# DC_DC_CONTROL.net
KiCad netlist of a schematic drawn in Altium Designer
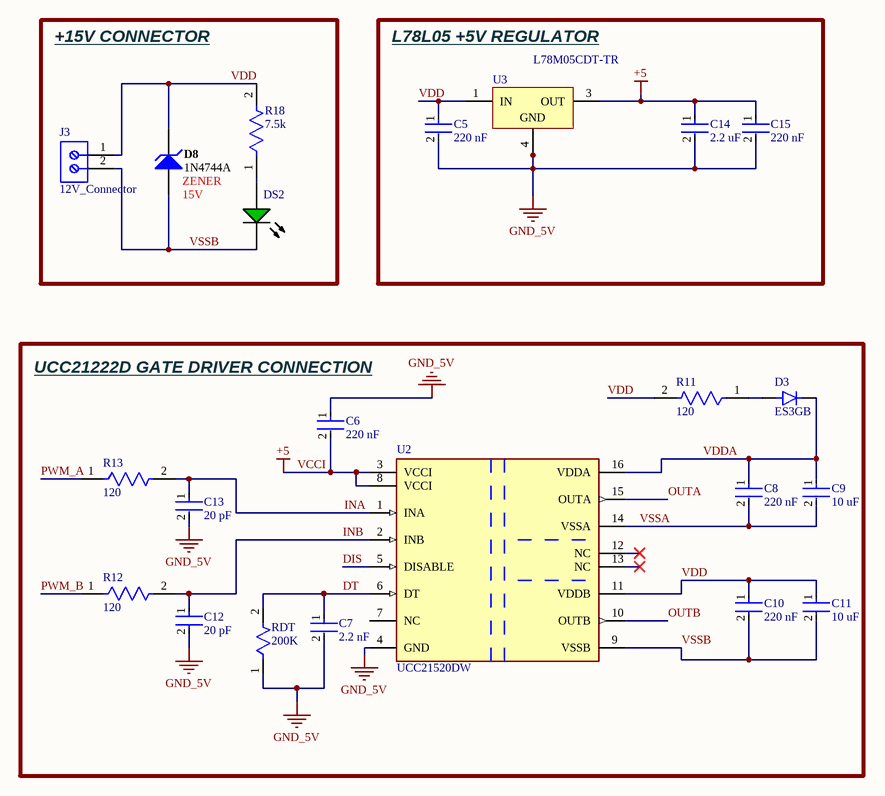
[diagram p0: DC_DC_CONTROL.SchDoc]

(export (version "E")
  (design (tool "Eeschema 10.0.6"))
  (components
    (comp (ref "C5")
      (value "220 nF")
      (footprint "FP-C0805C-DN-MFG")
      (description "CAP CER 0.22UF 50V X7R 0805")
      (fields
        (field (name "MANUFACTURER") "KEMET")
        (field (name "OCTOPART") "https://octopart.com/c0805c224k5ractu-kemet-144670")
      )
      (libsource (lib "Altium Content Vault") (part "b4654b650e69147ec39a6b967a45e02"))
    )
    (comp (ref "C6")
      (value "220 nF")
      (footprint "FP-C0805C-DN-MFG")
      (description "CAP CER 0.22UF 50V X7R 0805")
      (fields
        (field (name "MANUFACTURER") "KEMET")
        (field (name "OCTOPART") "https://octopart.com/c0805c224k5ractu-kemet-144670")
      )
      (libsource (lib "Altium Content Vault") (part "b4654b650e69147ec39a6b967a45e02"))
    )
    (comp (ref "C7")
      (value "2.2 nF")
      (footprint "FP-C0805C-DN-MFG")
      (description "CAP CER 0.22UF 50V X7R 0805")
      (fields
        (field (name "MANUFACTURER") "KEMET")
        (field (name "OCTOPART") "https://octopart.com/c0805c224k5ractu-kemet-144670")
      )
      (libsource (lib "Altium Content Vault") (part "b4654b650e69147ec39a6b967a45e02"))
    )
    (comp (ref "C8")
      (value "220 nF")
      (footprint "FP-C0805C-DN-MFG")
      (description "CAP CER 0.22UF 50V X7R 0805")
      (fields
        (field (name "MANUFACTURER") "KEMET")
        (field (name "OCTOPART") "https://octopart.com/c0805c224k5ractu-kemet-144670")
      )
      (libsource (lib "Altium Content Vault") (part "b4654b650e69147ec39a6b967a45e02"))
    )
    (comp (ref "C9")
      (value "10 uF")
      (footprint "FP-C0805C-DN-MFG")
      (description "CAP CER 0.22UF 50V X7R 0805")
      (fields
        (field (name "MANUFACTURER") "KEMET")
        (field (name "OCTOPART") "https://octopart.com/c0805c224k5ractu-kemet-144670")
      )
      (libsource (lib "Altium Content Vault") (part "b4654b650e69147ec39a6b967a45e02"))
    )
    (comp (ref "C10")
      (value "220 nF")
      (footprint "FP-C0805C-DN-MFG")
      (description "CAP CER 0.22UF 50V X7R 0805")
      (fields
        (field (name "MANUFACTURER") "KEMET")
        (field (name "OCTOPART") "https://octopart.com/c0805c224k5ractu-kemet-144670")
      )
      (libsource (lib "Altium Content Vault") (part "b4654b650e69147ec39a6b967a45e02"))
    )
    (comp (ref "C11")
      (value "10 uF")
      (footprint "FP-C0805C-DN-MFG")
      (description "CAP CER 0.22UF 50V X7R 0805")
      (fields
        (field (name "MANUFACTURER") "KEMET")
        (field (name "OCTOPART") "https://octopart.com/c0805c224k5ractu-kemet-144670")
      )
      (libsource (lib "Altium Content Vault") (part "b4654b650e69147ec39a6b967a45e02"))
    )
    (comp (ref "C12")
      (value "20 pF")
      (footprint "FP-C0805C-DN-MFG")
      (description "CAP CER 0.22UF 50V X7R 0805")
      (fields
        (field (name "MANUFACTURER") "KEMET")
        (field (name "OCTOPART") "https://octopart.com/c0805c224k5ractu-kemet-144670")
      )
      (libsource (lib "Altium Content Vault") (part "b4654b650e69147ec39a6b967a45e02"))
    )
    (comp (ref "C13")
      (value "20 pF")
      (footprint "FP-C0805C-DN-MFG")
      (description "CAP CER 0.22UF 50V X7R 0805")
      (fields
        (field (name "MANUFACTURER") "KEMET")
        (field (name "OCTOPART") "https://octopart.com/c0805c224k5ractu-kemet-144670")
      )
      (libsource (lib "Altium Content Vault") (part "b4654b650e69147ec39a6b967a45e02"))
    )
    (comp (ref "C14")
      (value "2.2 uF")
      (footprint "FP-C0805C-DN-MFG")
      (description "CAP CER 0.22UF 50V X7R 0805")
      (fields
        (field (name "MANUFACTURER") "KEMET")
        (field (name "OCTOPART") "https://octopart.com/c0805c224k5ractu-kemet-144670")
      )
      (libsource (lib "Altium Content Vault") (part "b4654b650e69147ec39a6b967a45e02"))
    )
    (comp (ref "C15")
      (value "220 nF")
      (footprint "FP-C0805C-DN-MFG")
      (description "CAP CER 0.22UF 50V X7R 0805")
      (fields
        (field (name "MANUFACTURER") "KEMET")
        (field (name "OCTOPART") "https://octopart.com/c0805c224k5ractu-kemet-144670")
      )
      (libsource (lib "Altium Content Vault") (part "b4654b650e69147ec39a6b967a45e02"))
    )
    (comp (ref "D3")
      (value "ES3GB")
      (footprint "ES3GB:DIOM4336X265N")
      (fields (field (name "MF") "{'manufacturer': u'Taiwan Semiconductor'}"))
      (libsource (lib "*") (part "ES3GB"))
    )
    (comp (ref "D8")
      (value "1N4744A")
      (footprint "FAIR-DO-41-2_V")
      (description "Zener Diode, 15V, 1W, 5%, -65 to 200 degC, 2-Pin DO-41, Body 2.72 x 5.2 mm, RoHS")
      (fields (field (name "MANUFACTURER") "Fairchild Semiconductor") (field (name "TOLERANCE") "5%"))
      (libsource (lib "Altium Content Vault") (part "FAIR-DZEN-A1K2-2"))
    )
    (comp (ref "DS2")
      (value "HSMG-C170")
      (footprint "AVAG-HSMX-C170_V")
      (description "Chip LED, Green, 2.2 V, -40 to 85 degC, 2-Pin SMD, Pb-Free, Tape and Reel")
      (fields (field (name "MANUFACTURER") "Avago"))
      (libsource (lib "Altium Content Vault") (part "LED_GREEN_A1K2-2"))
    )
    (comp (ref "J3")
      (value "12V_Connector")
      (footprint "691214110002")
      (fields (field (name "VOLTAGE") "300V"))
      (libsource (lib "WurthElectronics2PinTerminalBlock") (part "CMP-1502-02464-2"))
    )
    (comp (ref "R11")
      (value "120")
      (footprint "FP-RC0805-0_6-IPC_C")
      (description "120  1/8W   0805")
      (fields (field (name "TOLERANCE") "1%"))
      (libsource (lib "Altium Content Vault") (part "1029c3af85768c4190bb7ad29bc67b5"))
    )
    (comp (ref "R12")
      (value "120")
      (footprint "FP-RC0805-0_6-IPC_C")
      (description "120  1/8W   0805")
      (fields (field (name "TOLERANCE") "1%"))
      (libsource (lib "Altium Content Vault") (part "1029c3af85768c4190bb7ad29bc67b5"))
    )
    (comp (ref "R13")
      (value "120")
      (footprint "FP-RC0805-0_6-IPC_C")
      (description "120  1/8W   0805")
      (fields (field (name "TOLERANCE") "1%"))
      (libsource (lib "Altium Content Vault") (part "1029c3af85768c4190bb7ad29bc67b5"))
    )
    (comp (ref "R18")
      (value "7.5k")
      (footprint "FP-RC0805-0_6-IPC_C")
      (description "7.5K  1/8W   0805")
      (fields (field (name "TOLERANCE") "1%"))
      (libsource (lib "Altium Content Vault") (part "1029c3af85768c4190bb7ad29bc67b5"))
    )
    (comp (ref "RDT")
      (value "200K")
      (footprint "PCBComponent_1")
      (libsource (lib "RES_0.125W_AXIAL") (part "RES"))
    )
    (comp (ref "U2")
      (value "UCC21520DW")
      (footprint "FP-DW0016B-MFG")
      (description "DGTL ISO 5.7KV GATE DRVR 16SOIC")
      (libsource (lib "Altium Content Vault") (part "6a37a0897a27c2327358918c0ee180b"))
    )
    (comp (ref "U3")
      (value "L78M05CDT-TR")
      (footprint "TO-252_L")
      (description "Positive Voltage Regulator, 5V, 3-Pin DPAK, Tape and Reel")
      (libsource (lib "Altium Content Vault") (part "PM-REG-L4940-SOT3"))
    )
  )
  (nets
    (net (code "1") (name "+5") (class "Default")
      (node (ref "C14") (pin "1") (pinfunction "1_1") (pintype "passive"))
      (node (ref "C15") (pin "1") (pinfunction "1_1") (pintype "passive"))
      (node (ref "C6") (pin "2") (pinfunction "2_2") (pintype "passive"))
      (node (ref "U2") (pin "3") (pinfunction "VCCI_3") (pintype "power_in"))
      (node (ref "U2") (pin "8") (pinfunction "VCCI_8") (pintype "power_in"))
      (node (ref "U3") (pin "3") (pinfunction "OUT_3") (pintype "power_in"))
    )
    (net (code "2") (name "/DIS") (class "Default")
      (node (ref "U2") (pin "5") (pinfunction "DISABLE_5") (pintype "input"))
    )
    (net (code "3") (name "/DT") (class "Default")
      (node (ref "C7") (pin "1") (pinfunction "1_1") (pintype "passive"))
      (node (ref "RDT") (pin "2") (pinfunction "2_2") (pintype "passive"))
      (node (ref "U2") (pin "6") (pinfunction "DT_6") (pintype "input"))
    )
    (net (code "4") (name "/INA") (class "Default")
      (node (ref "C13") (pin "1") (pinfunction "1_1") (pintype "passive"))
      (node (ref "R13") (pin "2") (pinfunction "2_2") (pintype "passive"))
      (node (ref "U2") (pin "1") (pinfunction "INA_1") (pintype "input"))
    )
    (net (code "5") (name "/INB") (class "Default")
      (node (ref "C12") (pin "1") (pinfunction "1_1") (pintype "passive"))
      (node (ref "R12") (pin "2") (pinfunction "2_2") (pintype "passive"))
      (node (ref "U2") (pin "2") (pinfunction "INB_2") (pintype "input"))
    )
    (net (code "6") (name "/OUTA") (class "Default")
      (node (ref "U2") (pin "15") (pinfunction "OUTA_15") (pintype "output"))
    )
    (net (code "7") (name "/OUTB") (class "Default")
      (node (ref "U2") (pin "10") (pinfunction "OUTB_10") (pintype "output"))
    )
    (net (code "8") (name "/PWM_A") (class "Default")
      (node (ref "R13") (pin "1") (pinfunction "1_1") (pintype "passive"))
    )
    (net (code "9") (name "/PWM_B") (class "Default")
      (node (ref "R12") (pin "1") (pinfunction "1_1") (pintype "passive"))
    )
    (net (code "10") (name "/VDD") (class "Default")
      (node (ref "C10") (pin "1") (pinfunction "1_1") (pintype "passive"))
      (node (ref "C11") (pin "1") (pinfunction "1_1") (pintype "passive"))
      (node (ref "C5") (pin "1") (pinfunction "1_1") (pintype "passive"))
      (node (ref "D8") (pin "2") (pinfunction "K_2") (pintype "passive"))
      (node (ref "J3") (pin "1") (pinfunction "1_1") (pintype "passive"))
      (node (ref "R11") (pin "2") (pinfunction "2_2") (pintype "passive"))
      (node (ref "R18") (pin "2") (pinfunction "2_2") (pintype "passive"))
      (node (ref "U2") (pin "11") (pinfunction "VDDB_11") (pintype "power_in"))
      (node (ref "U3") (pin "1") (pinfunction "IN_1") (pintype "power_in"))
    )
    (net (code "11") (name "/VDDA") (class "Default")
      (node (ref "C8") (pin "1") (pinfunction "1_1") (pintype "passive"))
      (node (ref "C9") (pin "1") (pinfunction "1_1") (pintype "passive"))
      (node (ref "D3") (pin "C") (pinfunction "K_C") (pintype "passive"))
      (node (ref "U2") (pin "16") (pinfunction "VDDA_16") (pintype "power_in"))
    )
    (net (code "12") (name "/VSSA") (class "Default")
      (node (ref "C8") (pin "2") (pinfunction "2_2") (pintype "passive"))
      (node (ref "C9") (pin "2") (pinfunction "2_2") (pintype "passive"))
      (node (ref "U2") (pin "14") (pinfunction "VSSA_14") (pintype "power_in"))
    )
    (net (code "13") (name "/VSSB") (class "Default")
      (node (ref "C10") (pin "2") (pinfunction "2_2") (pintype "passive"))
      (node (ref "C11") (pin "2") (pinfunction "2_2") (pintype "passive"))
      (node (ref "D8") (pin "1") (pinfunction "A_1") (pintype "passive"))
      (node (ref "DS2") (pin "2") (pinfunction "K_2") (pintype "passive"))
      (node (ref "J3") (pin "2") (pinfunction "2_2") (pintype "passive"))
      (node (ref "U2") (pin "9") (pinfunction "VSSB_9") (pintype "power_in"))
    )
    (net (code "14") (name "GND_5V") (class "Default")
      (node (ref "C12") (pin "2") (pinfunction "2_2") (pintype "passive"))
      (node (ref "C13") (pin "2") (pinfunction "2_2") (pintype "passive"))
      (node (ref "C14") (pin "2") (pinfunction "2_2") (pintype "passive"))
      (node (ref "C15") (pin "2") (pinfunction "2_2") (pintype "passive"))
      (node (ref "C5") (pin "2") (pinfunction "2_2") (pintype "passive"))
      (node (ref "C6") (pin "1") (pinfunction "1_1") (pintype "passive"))
      (node (ref "C7") (pin "2") (pinfunction "2_2") (pintype "passive"))
      (node (ref "RDT") (pin "1") (pinfunction "1_1") (pintype "passive"))
      (node (ref "U2") (pin "4") (pinfunction "GND_4") (pintype "power_in"))
      (node (ref "U3") (pin "4") (pinfunction "GND_4") (pintype "power_in"))
    )
    (net (code "15") (name "Net-(D3-PadA)") (class "Default")
      (node (ref "D3") (pin "A") (pinfunction "A_A") (pintype "passive"))
      (node (ref "R11") (pin "1") (pinfunction "1_1") (pintype "passive"))
    )
    (net (code "16") (name "Net-(DS2-A)") (class "Default")
      (node (ref "DS2") (pin "1") (pinfunction "A_1") (pintype "passive"))
      (node (ref "R18") (pin "1") (pinfunction "1_1") (pintype "passive"))
    )
    (net (code "17") (name "unconnected-(U2-NC-Pad7)") (class "Default")
      (node (ref "U2") (pin "7") (pinfunction "NC_7") (pintype "passive"))
    )
    (net (code "18") (name "unconnected-(U2-NC-Pad12)") (class "Default")
      (node (ref "U2") (pin "12") (pinfunction "NC_12") (pintype "passive+no_connect"))
    )
    (net (code "19") (name "unconnected-(U2-NC-Pad13)") (class "Default")
      (node (ref "U2") (pin "13") (pinfunction "NC_13") (pintype "passive+no_connect"))
    )
  )
)
